# Doorsensor_433MHz.net
KiCad netlist of a schematic drawn in Altium Designer
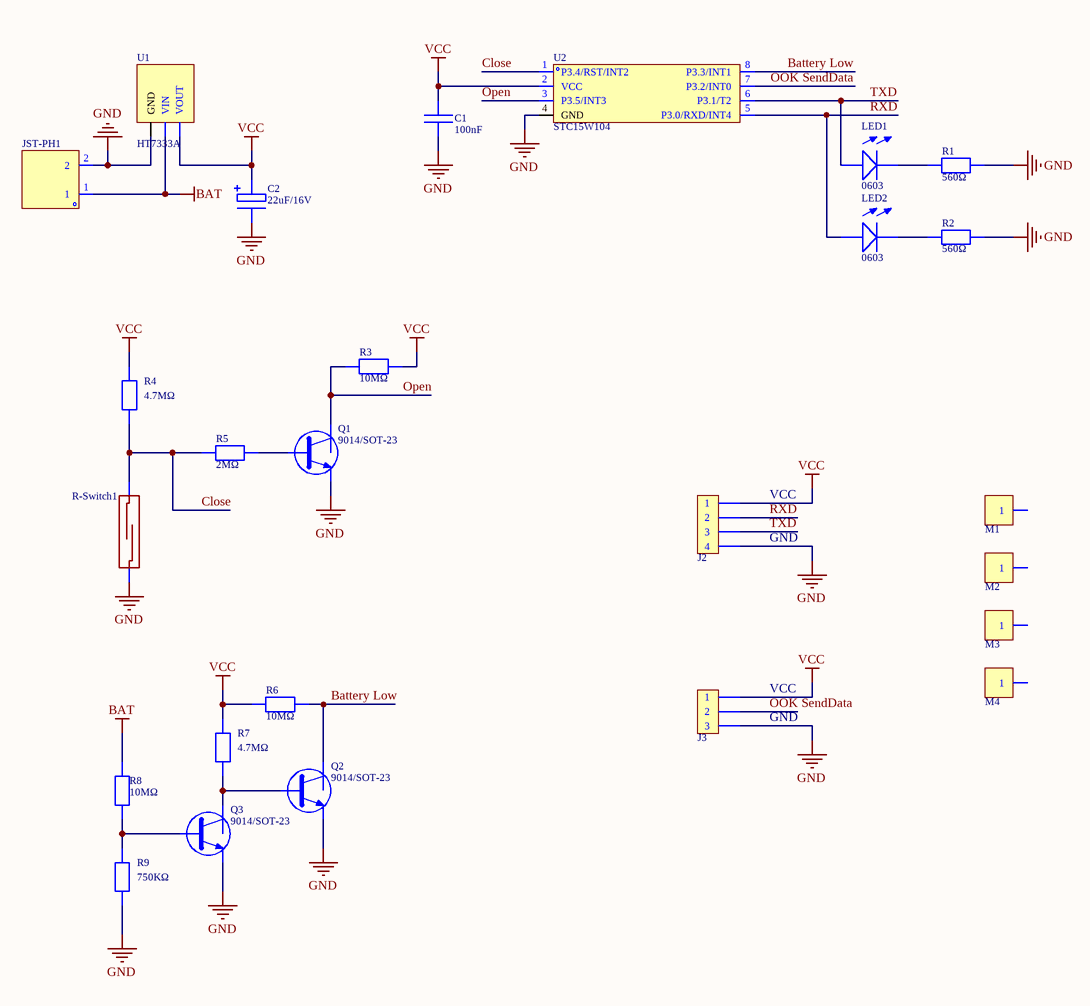
[diagram p0: Doorsensor_433MHz.SchDoc]

(export (version "E")
  (design (tool "Eeschema 10.0.6"))
  (components
    (comp (ref "C1")
      (value "100nF")
      (footprint "C0603")
      (libsource (lib "Schematic Library_General") (part "Capacitor_0603"))
    )
    (comp (ref "C2")
      (value "22uF/16V")
      (footprint "C(Electrolytic)_SMD-D4.0mm_L5.4mm")
      (libsource (lib "Schematic Library_General") (part "Capacitor_Electrolytic-SMD-D4.0xL5.4mm"))
    )
    (comp (ref "J2")
      (value "PinHeader_4Pin")
      (footprint "PinHeader_4Pin-2.54mm")
      (description "Straight Single Row, Square Pitch, 2.54mm")
      (libsource (lib "Schematic Library_General") (part "PinHeader_4Pin"))
    )
    (comp (ref "J3")
      (value "PinHeader_3Pin")
      (footprint "PinSocket_3Pin-2.54mm")
      (description "Straight Single Row, Square Pitch, 2.54mm")
      (libsource (lib "Schematic Library_General") (part "PinHeader_3Pin"))
    )
    (comp (ref "JST-PH1")
      (value "JST-PH2.0_2Pin-TH-Vertical")
      (footprint "Connector-JST-PH2.0-2Pin_TH-Vertical")
      (libsource (lib "Schematic Library_General") (part "JST-PH2.0_2Pin-TH-Vertical"))
    )
    (comp (ref "LED1")
      (value "0603")
      (footprint "LED0603-Castellated")
      (libsource (lib "Schematic Library_General") (part "LED_0603"))
    )
    (comp (ref "LED2")
      (value "0603")
      (footprint "LED0603-Castellated")
      (libsource (lib "Schematic Library_General") (part "LED_0603"))
    )
    (comp (ref "M1")
      (value "PCB Mounting Hole")
      (footprint "PCB Mounting Hole")
      (description "Mounting Hole")
      (libsource (lib "Schematic Library_General") (part "PCB Mounting Hole"))
    )
    (comp (ref "M2")
      (value "PCB Mounting Hole")
      (footprint "PCB Mounting Hole")
      (description "Mounting Hole")
      (libsource (lib "Schematic Library_General") (part "PCB Mounting Hole"))
    )
    (comp (ref "M3")
      (value "PCB Mounting Hole")
      (footprint "PCB Mounting Hole")
      (description "Mounting Hole")
      (libsource (lib "Schematic Library_General") (part "PCB Mounting Hole"))
    )
    (comp (ref "M4")
      (value "PCB Mounting Hole")
      (footprint "PCB Mounting Hole")
      (description "Mounting Hole")
      (libsource (lib "Schematic Library_General") (part "PCB Mounting Hole"))
    )
    (comp (ref "Q1")
      (value "9014/SOT-23")
      (footprint "SOT-23-3")
      (libsource (lib "Schematic Library_General") (part "NPN_SOT-23-3"))
    )
    (comp (ref "Q2")
      (value "9014/SOT-23")
      (footprint "SOT-23-3")
      (libsource (lib "Schematic Library_General") (part "NPN_SOT-23-3"))
    )
    (comp (ref "Q3")
      (value "9014/SOT-23")
      (footprint "SOT-23-3")
      (libsource (lib "Schematic Library_General") (part "NPN_SOT-23-3"))
    )
    (comp (ref "R-Switch1")
      (value "CT10-G1")
      (footprint "Reed Switch_Molded-SMD_SPST")
      (libsource (lib "Schematic Library_General") (part "Reed-Switch_Molded-SMD"))
    )
    (comp (ref "R1") (value "560Ω") (footprint "R0603") (libsource (lib "") (part "Resistor_0603_1")))
    (comp (ref "R2") (value "560Ω") (footprint "R0603") (libsource (lib "") (part "Resistor_0603_1")))
    (comp (ref "R3") (value "10MΩ") (footprint "R0603") (libsource (lib "") (part "Resistor_0603_1")))
    (comp (ref "R4")
      (value "4.7MΩ")
      (footprint "R0603")
      (libsource (lib "Schematic Library_General") (part "Resistor_0603"))
    )
    (comp (ref "R5") (value "2MΩ") (footprint "R0603") (libsource (lib "") (part "Resistor_0603_1")))
    (comp (ref "R6") (value "10MΩ") (footprint "R0603") (libsource (lib "") (part "Resistor_0603_1")))
    (comp (ref "R7")
      (value "4.7MΩ")
      (footprint "R0603")
      (libsource (lib "Schematic Library_General") (part "Resistor_0603"))
    )
    (comp (ref "R8")
      (value "10MΩ")
      (footprint "R0603")
      (libsource (lib "Schematic Library_General") (part "Resistor_0603"))
    )
    (comp (ref "R9")
      (value "750KΩ")
      (footprint "R0603")
      (libsource (lib "Schematic Library_General") (part "Resistor_0603"))
    )
    (comp (ref "U1")
      (value "HT7333A")
      (footprint "SOT89-3")
      (libsource (lib "Schematic Library_General") (part "LDO_SOT89-3"))
    )
    (comp (ref "U2")
      (value "STC15W104")
      (footprint "SOIC_8Pin-L5.0-W4.0")
      (libsource (lib "Schematic Library_General") (part "STC15W104_SOP8"))
    )
  )
  (nets
    (net (code "1") (name "/Battery Low") (class "Default")
      (node (ref "Q2") (pin "3") (pintype "passive"))
      (node (ref "R6") (pin "2") (pintype "passive"))
      (node (ref "U2") (pin "8") (pinfunction "P3.3/INT1_8") (pintype "passive"))
    )
    (net (code "2") (name "/Close") (class "Default")
      (node (ref "R-Switch1") (pin "2") (pintype "passive"))
      (node (ref "R4") (pin "1") (pintype "passive"))
      (node (ref "R5") (pin "1") (pintype "passive"))
      (node (ref "U2") (pin "1") (pinfunction "P3.4/RST/INT2_1") (pintype "passive"))
    )
    (net (code "3") (name "/OOK SendData") (class "Default")
      (node (ref "J3") (pin "2") (pinfunction "2_2") (pintype "passive"))
      (node (ref "U2") (pin "7") (pinfunction "P3.2/INT0_7") (pintype "passive"))
    )
    (net (code "4") (name "/Open") (class "Default")
      (node (ref "Q1") (pin "3") (pintype "passive"))
      (node (ref "R3") (pin "1") (pintype "passive"))
      (node (ref "U2") (pin "3") (pinfunction "P3.5/INT3_3") (pintype "passive"))
    )
    (net (code "5") (name "/RXD") (class "Default")
      (node (ref "J2") (pin "2") (pinfunction "2_2") (pintype "passive"))
      (node (ref "LED2") (pin "1") (pintype "passive"))
      (node (ref "U2") (pin "5") (pinfunction "P3.0/RXD/INT4_5") (pintype "passive"))
    )
    (net (code "6") (name "/TXD") (class "Default")
      (node (ref "J2") (pin "3") (pinfunction "3_3") (pintype "passive"))
      (node (ref "LED1") (pin "1") (pintype "passive"))
      (node (ref "U2") (pin "6") (pinfunction "P3.1/T2_6") (pintype "passive"))
    )
    (net (code "7") (name "BAT") (class "Default")
      (node (ref "JST-PH1") (pin "1") (pinfunction "1_1") (pintype "passive"))
      (node (ref "R8") (pin "2") (pintype "passive"))
      (node (ref "U1") (pin "2") (pinfunction "VIN_2") (pintype "passive"))
    )
    (net (code "8") (name "GND") (class "Default")
      (node (ref "C1") (pin "1") (pintype "passive"))
      (node (ref "C2") (pin "2") (pintype "passive"))
      (node (ref "J2") (pin "4") (pinfunction "4_4") (pintype "passive"))
      (node (ref "J3") (pin "3") (pinfunction "3_3") (pintype "passive"))
      (node (ref "JST-PH1") (pin "2") (pinfunction "2_2") (pintype "passive"))
      (node (ref "Q1") (pin "2") (pintype "passive"))
      (node (ref "Q2") (pin "2") (pintype "passive"))
      (node (ref "Q3") (pin "2") (pintype "passive"))
      (node (ref "R-Switch1") (pin "1") (pintype "passive"))
      (node (ref "R1") (pin "2") (pintype "passive"))
      (node (ref "R2") (pin "2") (pintype "passive"))
      (node (ref "R9") (pin "1") (pintype "passive"))
      (node (ref "U1") (pin "1") (pinfunction "GND_1") (pintype "passive"))
      (node (ref "U2") (pin "4") (pinfunction "GND_4") (pintype "passive"))
    )
    (net (code "9") (name "Net-(LED1-Pad2)") (class "Default")
      (node (ref "LED1") (pin "2") (pintype "passive"))
      (node (ref "R1") (pin "1") (pintype "passive"))
    )
    (net (code "10") (name "Net-(LED2-Pad2)") (class "Default")
      (node (ref "LED2") (pin "2") (pintype "passive"))
      (node (ref "R2") (pin "1") (pintype "passive"))
    )
    (net (code "11") (name "Net-(Q1-Pad1)") (class "Default")
      (node (ref "Q1") (pin "1") (pintype "passive"))
      (node (ref "R5") (pin "2") (pintype "passive"))
    )
    (net (code "12") (name "Net-(Q2-Pad1)") (class "Default")
      (node (ref "Q2") (pin "1") (pintype "passive"))
      (node (ref "Q3") (pin "3") (pintype "passive"))
      (node (ref "R7") (pin "1") (pintype "passive"))
    )
    (net (code "13") (name "Net-(Q3-Pad1)") (class "Default")
      (node (ref "Q3") (pin "1") (pintype "passive"))
      (node (ref "R8") (pin "1") (pintype "passive"))
      (node (ref "R9") (pin "2") (pintype "passive"))
    )
    (net (code "14") (name "VCC") (class "Default")
      (node (ref "C1") (pin "2") (pintype "passive"))
      (node (ref "C2") (pin "1") (pintype "passive"))
      (node (ref "J2") (pin "1") (pinfunction "1_1") (pintype "passive"))
      (node (ref "J3") (pin "1") (pinfunction "1_1") (pintype "passive"))
      (node (ref "R3") (pin "2") (pintype "passive"))
      (node (ref "R4") (pin "2") (pintype "passive"))
      (node (ref "R6") (pin "1") (pintype "passive"))
      (node (ref "R7") (pin "2") (pintype "passive"))
      (node (ref "U1") (pin "3") (pinfunction "VOUT_3") (pintype "passive"))
      (node (ref "U2") (pin "2") (pinfunction "VCC_2") (pintype "passive"))
    )
    (net (code "15") (name "unconnected-(M1-Pad1)") (class "Default")
      (node (ref "M1") (pin "1") (pinfunction "1_1") (pintype "passive"))
    )
    (net (code "16") (name "unconnected-(M2-Pad1)") (class "Default")
      (node (ref "M2") (pin "1") (pinfunction "1_1") (pintype "passive"))
    )
    (net (code "17") (name "unconnected-(M3-Pad1)") (class "Default")
      (node (ref "M3") (pin "1") (pinfunction "1_1") (pintype "passive"))
    )
    (net (code "18") (name "unconnected-(M4-Pad1)") (class "Default")
      (node (ref "M4") (pin "1") (pinfunction "1_1") (pintype "passive"))
    )
  )
)
